# ZOPT220x_UV_Sensor_Breakout.net
KiCad netlist of a schematic drawn in EAGLE
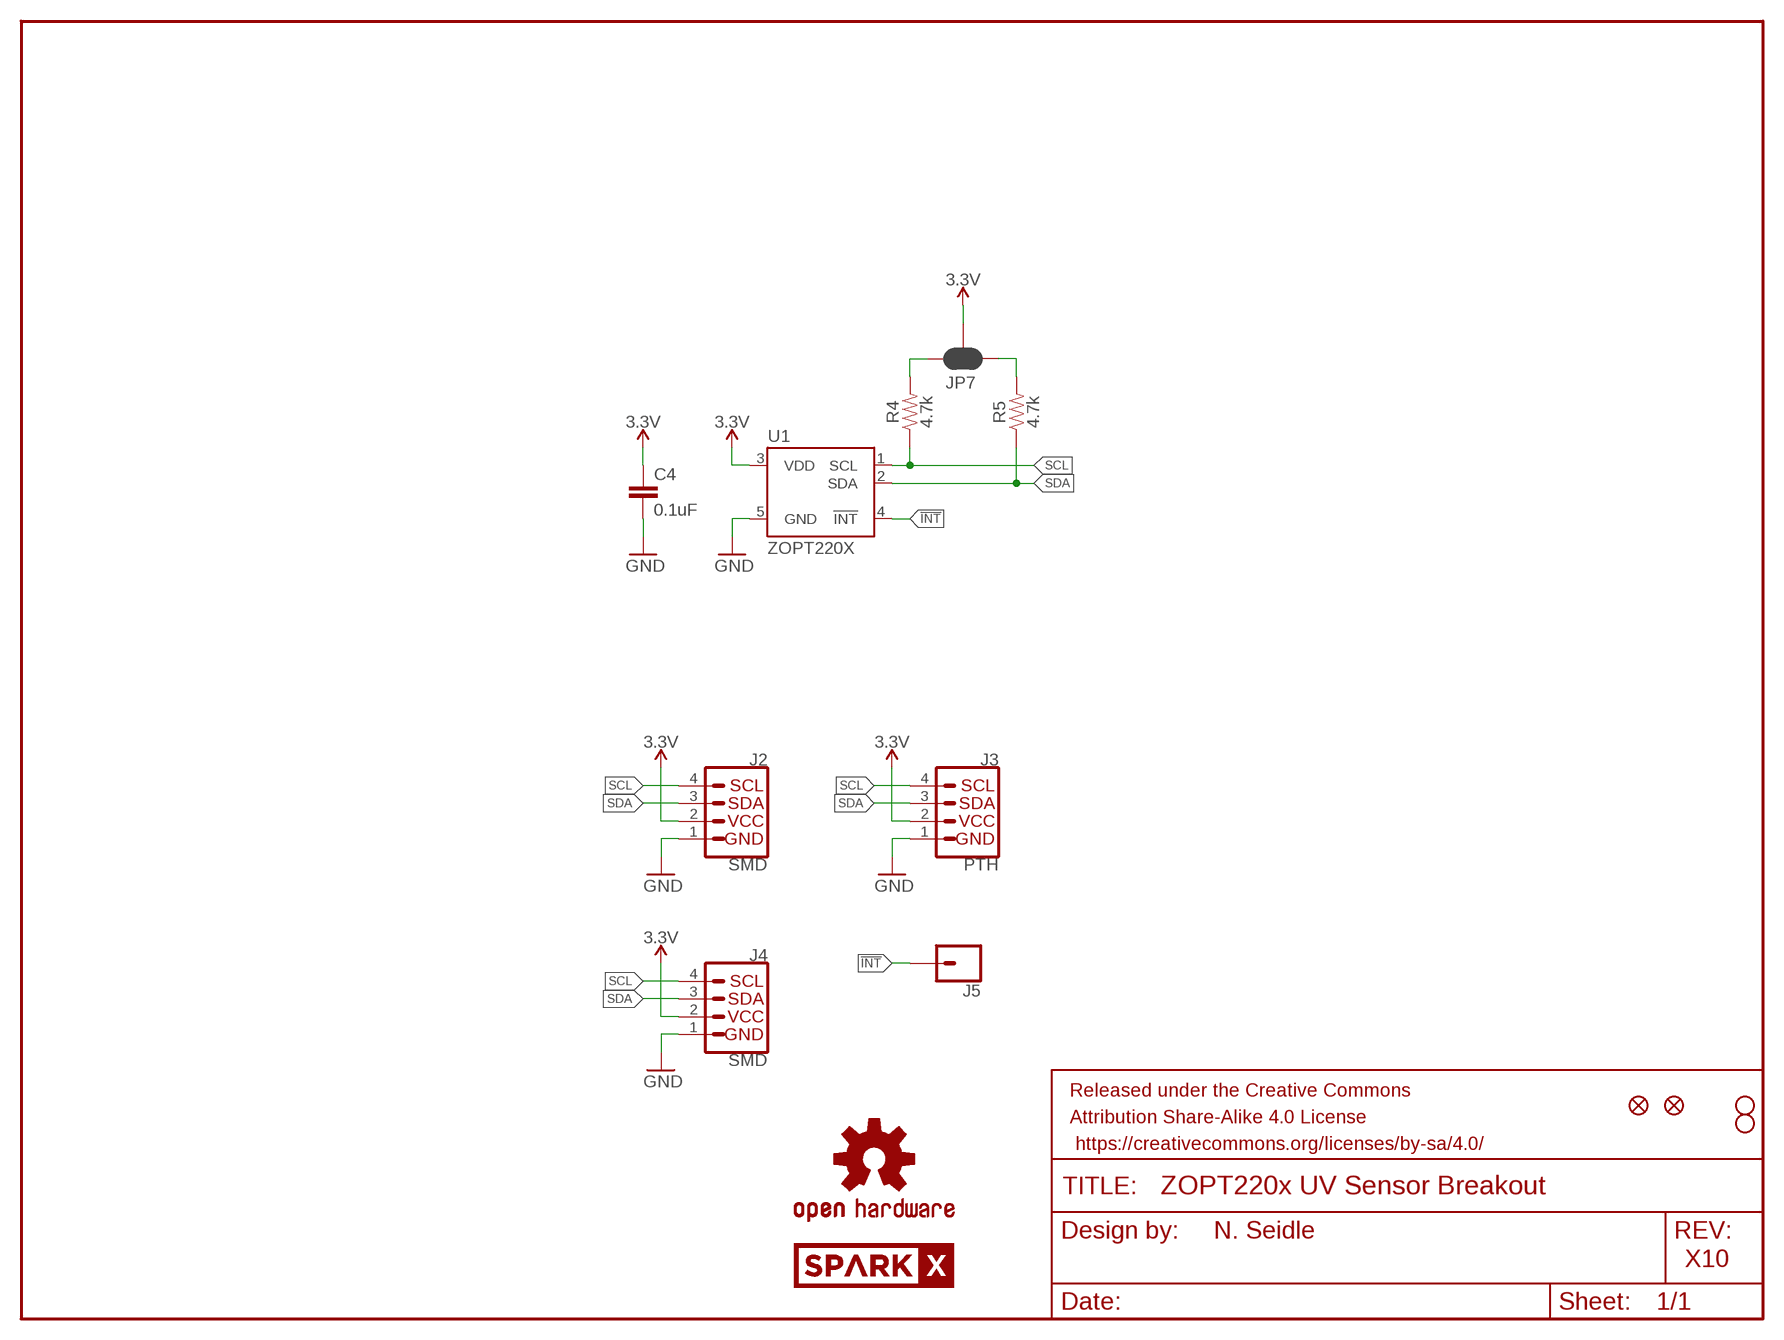
[diagram p0: schematic, sheet 1]

(export (version "E")
  (design (tool "Eeschema 10.0.6"))
  (components
    (comp (ref "C4")
      (value "0.1uF")
      (footprint "eagle-import:0603")
      (libsource (lib "eagle-import") (part "0.1UF-0603-25V-(+80/-20%)"))
    )
    (comp (ref "FRAME1")
      (value "FRAME-LETTER")
      (footprint "eagle-import:CREATIVE_COMMONS")
      (libsource (lib "eagle-import") (part "FRAME-LETTER"))
    )
    (comp (ref "J2")
      (value "SMD")
      (footprint "eagle-import:1X04_1MM_RA")
      (libsource (lib "eagle-import") (part "I2C_STANDARDJS-1MM"))
    )
    (comp (ref "J3")
      (value "PTH")
      (footprint "eagle-import:1X04_NO_SILK")
      (libsource (lib "eagle-import") (part "I2C_STANDARD_NO_SILK"))
    )
    (comp (ref "J4")
      (value "SMD")
      (footprint "eagle-import:1X04_1MM_RA")
      (libsource (lib "eagle-import") (part "I2C_STANDARDJS-1MM"))
    )
    (comp (ref "J5")
      (value "CONN_01PTH_NO_SILK_KIT")
      (footprint "eagle-import:1X01NS_KIT")
      (libsource (lib "eagle-import") (part "CONN_01PTH_NO_SILK_KIT"))
    )
    (comp (ref "JP2")
      (value "FIDUCIALUFIDUCIAL")
      (footprint "eagle-import:MICRO-FIDUCIAL")
      (libsource (lib "eagle-import") (part "FIDUCIALUFIDUCIAL"))
    )
    (comp (ref "JP3")
      (value "STAND-OFF")
      (footprint "eagle-import:STAND-OFF")
      (libsource (lib "eagle-import") (part "STAND-OFF"))
    )
    (comp (ref "JP4")
      (value "STAND-OFF")
      (footprint "eagle-import:STAND-OFF")
      (libsource (lib "eagle-import") (part "STAND-OFF"))
    )
    (comp (ref "JP6")
      (value "FIDUCIALUFIDUCIAL")
      (footprint "eagle-import:MICRO-FIDUCIAL")
      (libsource (lib "eagle-import") (part "FIDUCIALUFIDUCIAL"))
    )
    (comp (ref "JP7")
      (value "JUMPER-SMT_3_2-NC_PASTE_SILK")
      (footprint "eagle-import:SMT-JUMPER_3_2-NC_PASTE_SILK")
      (libsource (lib "eagle-import") (part "JUMPER-SMT_3_2-NC_PASTE_SILK"))
    )
    (comp (ref "LOGO1")
      (value "OSHW-LOGOMINI")
      (footprint "eagle-import:OSHW-LOGO-MINI")
      (libsource (lib "eagle-import") (part "OSHW-LOGOMINI"))
    )
    (comp (ref "R4")
      (value "4.7k")
      (footprint "eagle-import:0603")
      (libsource (lib "eagle-import") (part "4.7KOHM-0603-1/10W-1%"))
    )
    (comp (ref "R5")
      (value "4.7k")
      (footprint "eagle-import:0603")
      (libsource (lib "eagle-import") (part "4.7KOHM-0603-1/10W-1%"))
    )
    (comp (ref "U$1")
      (value "SPARKX-LOGO4")
      (footprint "eagle-import:SPARKX-MEDIUM")
      (libsource (lib "eagle-import") (part "SPARKX-LOGO4"))
    )
    (comp (ref "U$2")
      (value "SPARKX-LOGO4")
      (footprint "eagle-import:SPARKX-MEDIUM")
      (libsource (lib "eagle-import") (part "SPARKX-LOGO4"))
    )
    (comp (ref "U1")
      (value "ZOPT220X")
      (footprint "eagle-import:LGA6")
      (libsource (lib "eagle-import") (part "ZOPT220X"))
    )
  )
  (nets
    (net (code "1") (name "/~{INT}") (class "Default")
      (node (ref "J5") (pin "1") (pinfunction "1_1") (pintype "passive"))
      (node (ref "U1") (pin "4") (pinfunction "~{INT}_4") (pintype "bidirectional"))
    )
    (net (code "2") (name "3.3V") (class "Default")
      (node (ref "C4") (pin "1") (pinfunction "1_1") (pintype "passive"))
      (node (ref "J2") (pin "2") (pinfunction "VCC_2") (pintype "power_in"))
      (node (ref "J3") (pin "2") (pinfunction "VCC_2") (pintype "power_in"))
      (node (ref "J4") (pin "2") (pinfunction "VCC_2") (pintype "power_in"))
      (node (ref "JP7") (pin "2") (pinfunction "2_2") (pintype "passive"))
      (node (ref "U1") (pin "3") (pinfunction "VDD_3") (pintype "bidirectional"))
    )
    (net (code "3") (name "GND") (class "Default")
      (node (ref "C4") (pin "2") (pinfunction "2_2") (pintype "passive"))
      (node (ref "J2") (pin "1") (pinfunction "GND_1") (pintype "power_in"))
      (node (ref "J3") (pin "1") (pinfunction "GND_1") (pintype "power_in"))
      (node (ref "J4") (pin "1") (pinfunction "GND_1") (pintype "power_in"))
      (node (ref "U1") (pin "5") (pinfunction "GND_5") (pintype "bidirectional"))
    )
    (net (code "4") (name "Net-(JP7-Pad1)") (class "Default")
      (node (ref "JP7") (pin "1") (pinfunction "1_1") (pintype "passive"))
      (node (ref "R5") (pin "2") (pinfunction "2_2") (pintype "passive"))
    )
    (net (code "5") (name "Net-(JP7-Pad3)") (class "Default")
      (node (ref "JP7") (pin "3") (pinfunction "3_3") (pintype "passive"))
      (node (ref "R4") (pin "2") (pinfunction "2_2") (pintype "passive"))
    )
    (net (code "6") (name "SCL") (class "Default")
      (node (ref "J2") (pin "4") (pinfunction "SCL_4") (pintype "passive"))
      (node (ref "J3") (pin "4") (pinfunction "SCL_4") (pintype "passive"))
      (node (ref "J4") (pin "4") (pinfunction "SCL_4") (pintype "passive"))
      (node (ref "R4") (pin "1") (pinfunction "1_1") (pintype "passive"))
      (node (ref "U1") (pin "1") (pinfunction "SCL_1") (pintype "bidirectional"))
    )
    (net (code "7") (name "SDA") (class "Default")
      (node (ref "J2") (pin "3") (pinfunction "SDA_3") (pintype "passive"))
      (node (ref "J3") (pin "3") (pinfunction "SDA_3") (pintype "passive"))
      (node (ref "J4") (pin "3") (pinfunction "SDA_3") (pintype "passive"))
      (node (ref "R5") (pin "1") (pinfunction "1_1") (pintype "passive"))
      (node (ref "U1") (pin "2") (pinfunction "SDA_2") (pintype "bidirectional"))
    )
  )
)
